# Thermal_Gradient_Experiment_Board.net
KiCad netlist of a schematic drawn in EAGLE
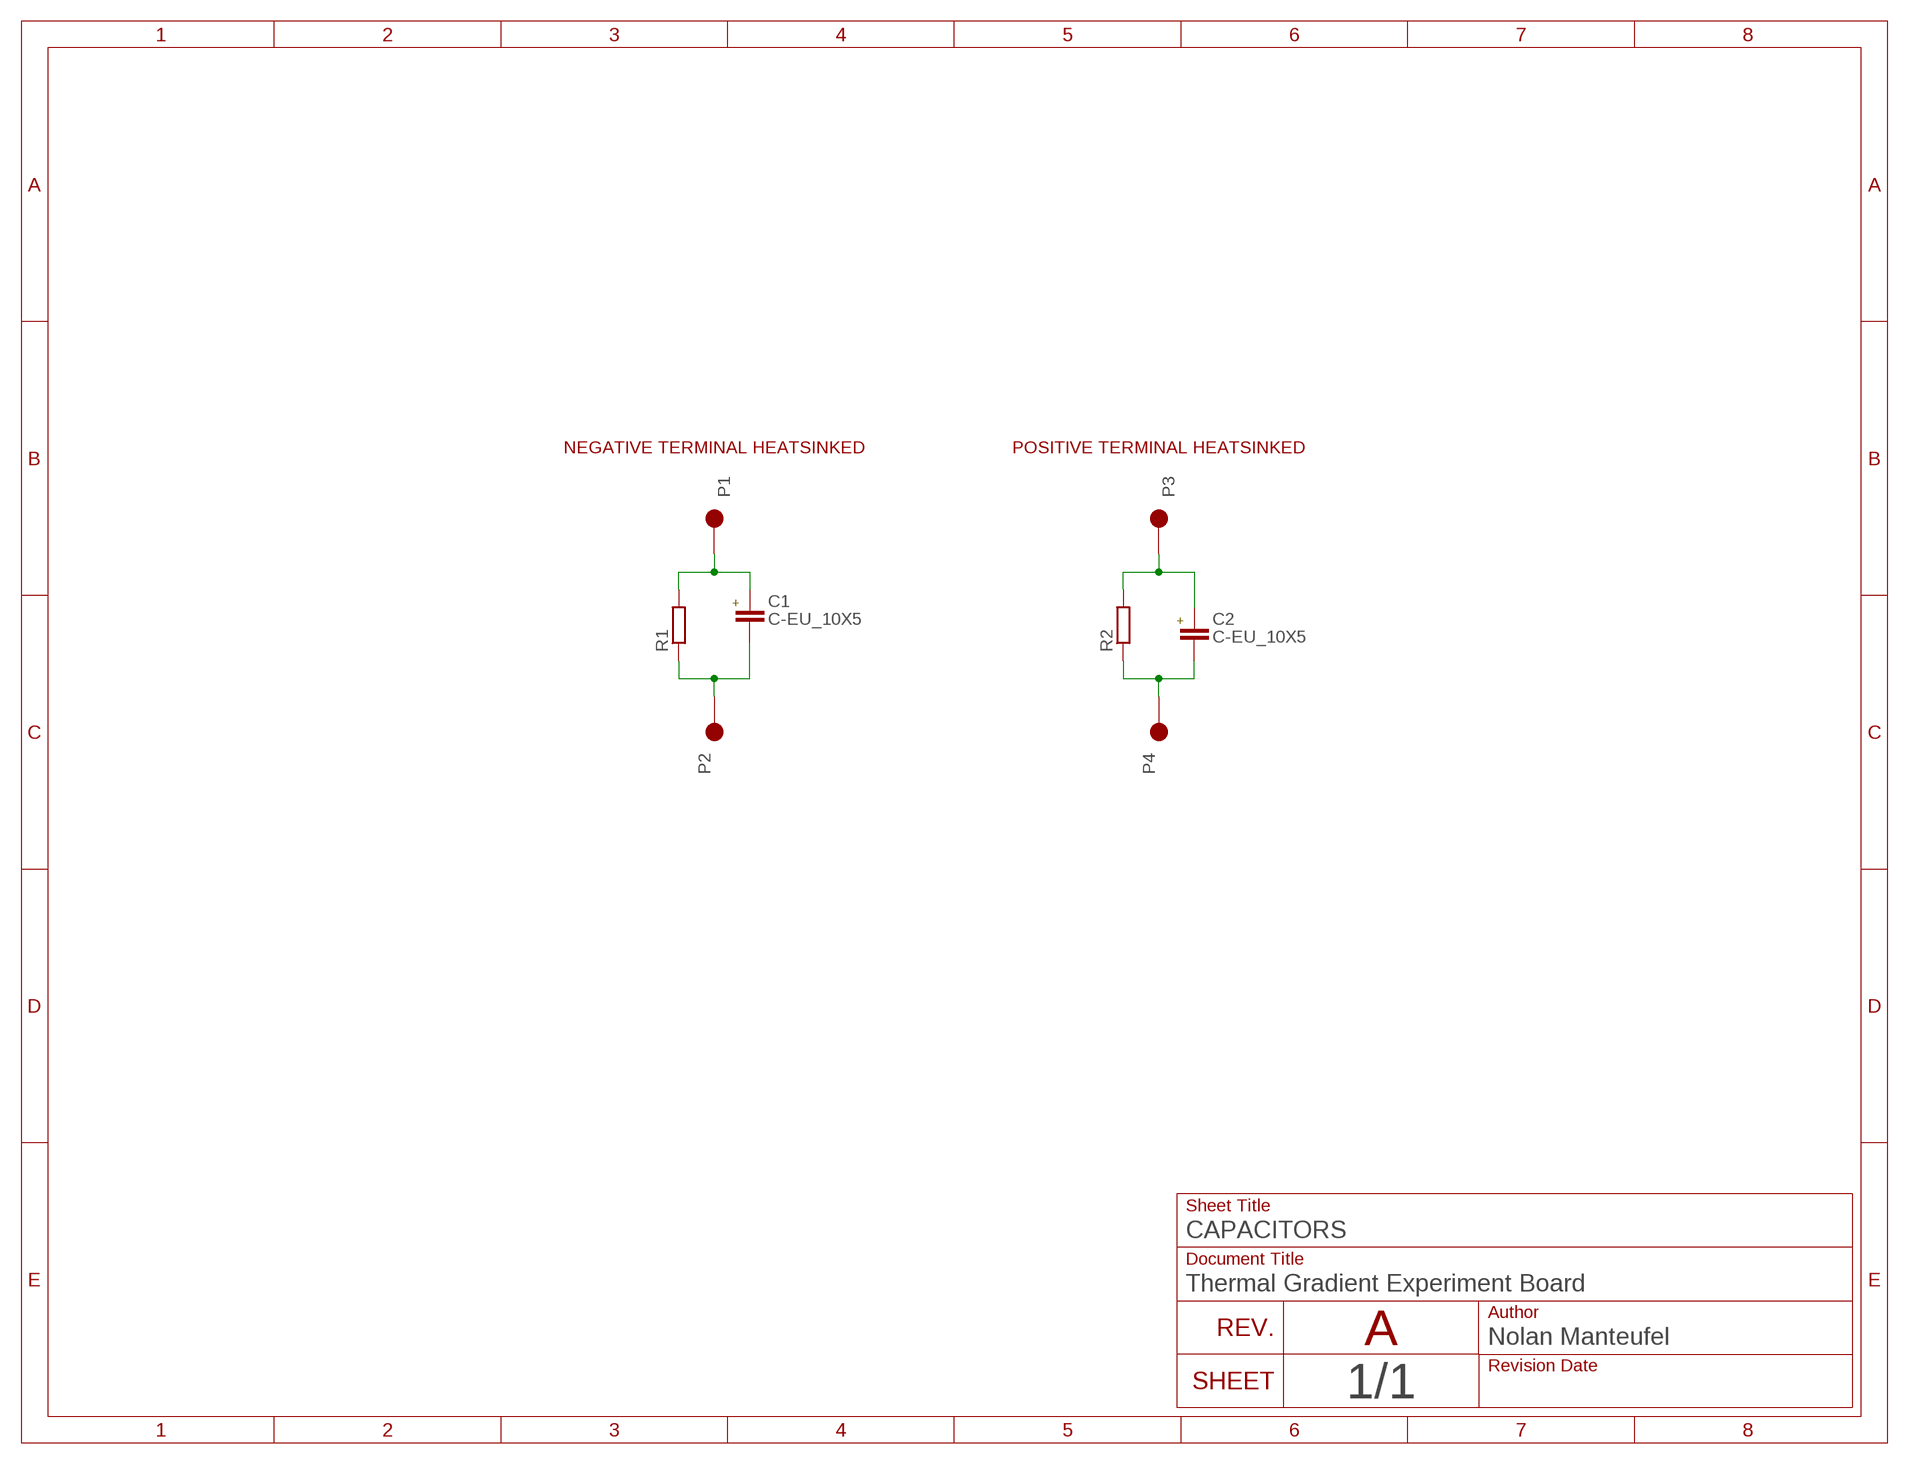
[diagram p0: schematic, sheet 1]

(export (version "E")
  (design (tool "Eeschema 10.0.6"))
  (components
    (comp (ref "C1")
      (value "C-EU_10X5")
      (footprint "eagle-import:C_PZF_10")
      (libsource (lib "eagle-import") (part "C-EU_10X5"))
    )
    (comp (ref "C2")
      (value "C-EU_10X5")
      (footprint "eagle-import:C_PZF_10")
      (libsource (lib "eagle-import") (part "C-EU_10X5"))
    )
    (comp (ref "P1")
      (value "PINS_1_2MM2")
      (footprint "eagle-import:PINS_1_2MM2")
      (libsource (lib "eagle-import") (part "PINS_1_2MM2"))
    )
    (comp (ref "P2")
      (value "PINS_1_2MM2")
      (footprint "eagle-import:PINS_1_2MM2")
      (libsource (lib "eagle-import") (part "PINS_1_2MM2"))
    )
    (comp (ref "P3")
      (value "PINS_1_2MM2")
      (footprint "eagle-import:PINS_1_2MM2")
      (libsource (lib "eagle-import") (part "PINS_1_2MM2"))
    )
    (comp (ref "P4")
      (value "PINS_1_2MM2")
      (footprint "eagle-import:PINS_1_2MM2")
      (libsource (lib "eagle-import") (part "PINS_1_2MM2"))
    )
    (comp (ref "R1")
      (value "R-EU__VISHAY_THJP1225AST1")
      (footprint "eagle-import:R_THERMAL_1225")
      (libsource (lib "eagle-import") (part "R-EU__VISHAY_THJP1225AST1"))
    )
    (comp (ref "R2")
      (value "R-EU__VISHAY_THJP1225AST1")
      (footprint "eagle-import:R_THERMAL_1225")
      (libsource (lib "eagle-import") (part "R-EU__VISHAY_THJP1225AST1"))
    )
  )
  (nets
    (net (code "1") (name "Net-(C1-1)") (class "Default")
      (node (ref "C1") (pin "1+") (pinfunction "1_1+") (pintype "passive"))
      (node (ref "P1") (pin "1") (pinfunction "1_1") (pintype "bidirectional"))
      (node (ref "R1") (pin "2") (pinfunction "2_2") (pintype "passive"))
    )
    (net (code "2") (name "Net-(C1-2)") (class "Default")
      (node (ref "C1") (pin "2-") (pinfunction "2_2-") (pintype "passive"))
      (node (ref "P2") (pin "1") (pinfunction "1_1") (pintype "bidirectional"))
      (node (ref "R1") (pin "1") (pinfunction "1_1") (pintype "passive"))
    )
    (net (code "3") (name "Net-(C2-1)") (class "Default")
      (node (ref "C2") (pin "1+") (pinfunction "1_1+") (pintype "passive"))
      (node (ref "P3") (pin "1") (pinfunction "1_1") (pintype "bidirectional"))
      (node (ref "R2") (pin "2") (pinfunction "2_2") (pintype "passive"))
    )
    (net (code "4") (name "Net-(C2-2)") (class "Default")
      (node (ref "C2") (pin "2-") (pinfunction "2_2-") (pintype "passive"))
      (node (ref "P4") (pin "1") (pinfunction "1_1") (pintype "bidirectional"))
      (node (ref "R2") (pin "1") (pinfunction "1_1") (pintype "passive"))
    )
  )
)
